# CAN.net
KiCad netlist of a schematic drawn in Altium Designer
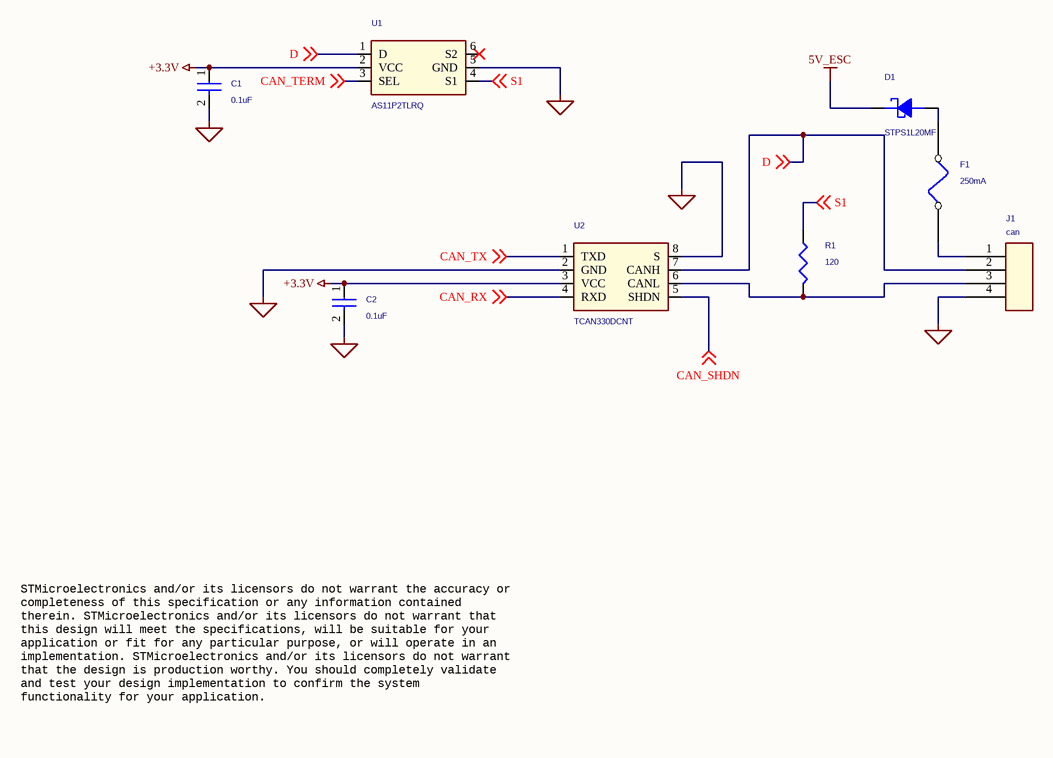
[diagram p0: CAN.SchDoc]

(export (version "E")
  (design (tool "Eeschema 10.0.6"))
  (components
    (comp (ref "C1")
      (value "0.1uF")
      (footprint "C_0402")
      (description "CAP CER 0.1UF 16V X7R 0402")
      (fields (field (name "PART_NUMBER") "CAP-00000053") (field (name "TOLERANCE") "10%"))
      (libsource (lib "*") (part "CAP_Dup1"))
    )
    (comp (ref "C2")
      (value "0.1uF")
      (footprint "C_0402")
      (description "CAP CER 0.1UF 16V X7R 0402")
      (fields (field (name "PART_NUMBER") "CAP-00000053") (field (name "TOLERANCE") "10%"))
      (libsource (lib "*") (part "CAP_Dup1"))
    )
    (comp (ref "D1")
      (value "STPS1L20MF")
      (footprint "do216-aa-flat")
      (description "DIODE SCHOTTKY 20V 1A STMITEFLAT")
      (fields (field (name "MANUFACTURER") "STMicroelectronics") (field (name "PART_NUMBER") "TMP-380"))
      (libsource (lib "*") (part "DIODE_SCHOTTKY_0"))
    )
    (comp (ref "F1")
      (value "250mA")
      (footprint "f_0402")
      (description "FUSE BOARD MNT 250MA 32VDC 0402")
      (fields (field (name "MANUFACTURER") "Littelfuse Inc.") (field (name "PART_NUMBER") "TMP-439"))
      (libsource (lib "*") (part "FUSE"))
    )
    (comp (ref "J1")
      (value "can")
      (footprint "SOLDER_PAD_4PIN_SMD")
      (description "SOLDER PADS")
      (libsource (lib "*") (part "CON4"))
    )
    (comp (ref "R1")
      (value "120")
      (footprint "R_0402")
      (description "RES SMD 120 OHM 1% 1/16W 0402")
      (fields (field (name "PART_NUMBER") "TMP-441") (field (name "TOLERANCE") "1%"))
      (libsource (lib "*") (part "RES"))
    )
    (comp (ref "U1")
      (value "AS11P2TLRQ")
      (footprint "son6p40_120x100x55l35x20")
      (description "IC ANLG SWITCH SGL SPDT 6QFN")
      (fields (field (name "MANUFACTURER") "STMicroelectronics") (field (name "PART_NUMBER") "TMP-378"))
      (libsource (lib "*") (part "AS11P2TLR"))
    )
    (comp (ref "U2")
      (value "TCAN330DCNT")
      (footprint "sot23-8p65_280x145l45x30n")
      (description "IC TXRX CAN 3.3V SOT-23")
      (fields (field (name "PART_NUMBER") "TMP-379") (field (name "MANUFACTURER") "Texas Instruments"))
      (libsource (lib "*") (part "TCAN330"))
    )
  )
  (nets
    (net (code "1") (name "+3.3V") (class "Default")
      (node (ref "C1") (pin "1") (pinfunction "1_1") (pintype "passive"))
      (node (ref "C2") (pin "1") (pinfunction "1_1") (pintype "passive"))
      (node (ref "U1") (pin "2") (pinfunction "VCC_2") (pintype "passive"))
      (node (ref "U2") (pin "3") (pinfunction "VCC_3") (pintype "passive"))
    )
    (net (code "2") (name "5V_ESC") (class "Default")
      (node (ref "D1") (pin "C") (pinfunction "C_C") (pintype "passive"))
    )
    (net (code "3") (name "CAN_RX") (class "Default")
      (node (ref "U2") (pin "4") (pinfunction "RXD_4") (pintype "passive"))
    )
    (net (code "4") (name "CAN_SHDN") (class "Default")
      (node (ref "U2") (pin "5") (pinfunction "SHDN_5") (pintype "passive"))
    )
    (net (code "5") (name "CAN_TERM") (class "Default")
      (node (ref "U1") (pin "3") (pinfunction "SEL_3") (pintype "passive"))
    )
    (net (code "6") (name "CAN_TX") (class "Default")
      (node (ref "U2") (pin "1") (pinfunction "TXD_1") (pintype "passive"))
    )
    (net (code "7") (name "D") (class "Default")
      (node (ref "J1") (pin "2") (pinfunction "2_2") (pintype "passive"))
      (node (ref "U1") (pin "1") (pinfunction "D_1") (pintype "passive"))
      (node (ref "U2") (pin "7") (pinfunction "CANH_7") (pintype "passive"))
    )
    (net (code "8") (name "GND_SIGNAL") (class "Default")
      (node (ref "C1") (pin "2") (pinfunction "2_2") (pintype "passive"))
      (node (ref "C2") (pin "2") (pinfunction "2_2") (pintype "passive"))
      (node (ref "J1") (pin "4") (pinfunction "4_4") (pintype "passive"))
      (node (ref "U1") (pin "5") (pinfunction "GND_5") (pintype "passive"))
      (node (ref "U2") (pin "2") (pinfunction "GND_2") (pintype "passive"))
      (node (ref "U2") (pin "8") (pinfunction "S_8") (pintype "passive"))
    )
    (net (code "9") (name "Net-(D1-PadA)") (class "Default")
      (node (ref "D1") (pin "A") (pinfunction "A_A") (pintype "passive"))
      (node (ref "F1") (pin "2") (pinfunction "2_2") (pintype "passive"))
    )
    (net (code "10") (name "Net-(F1-Pad1)") (class "Default")
      (node (ref "F1") (pin "1") (pinfunction "1_1") (pintype "passive"))
      (node (ref "J1") (pin "1") (pinfunction "1_1") (pintype "passive"))
    )
    (net (code "11") (name "Net-(U2-CANL)") (class "Default")
      (node (ref "J1") (pin "3") (pinfunction "3_3") (pintype "passive"))
      (node (ref "R1") (pin "2") (pinfunction "2_2") (pintype "passive"))
      (node (ref "U2") (pin "6") (pinfunction "CANL_6") (pintype "passive"))
    )
    (net (code "12") (name "S1") (class "Default")
      (node (ref "R1") (pin "1") (pinfunction "1_1") (pintype "passive"))
      (node (ref "U1") (pin "4") (pinfunction "S1_4") (pintype "passive"))
    )
    (net (code "13") (name "unconnected-(U1-S2-Pad6)") (class "Default")
      (node (ref "U1") (pin "6") (pinfunction "S2_6") (pintype "passive+no_connect"))
    )
  )
)
